# 2014-09-02_05-44-381.net
KiCad netlist of a schematic drawn in Altium Designer
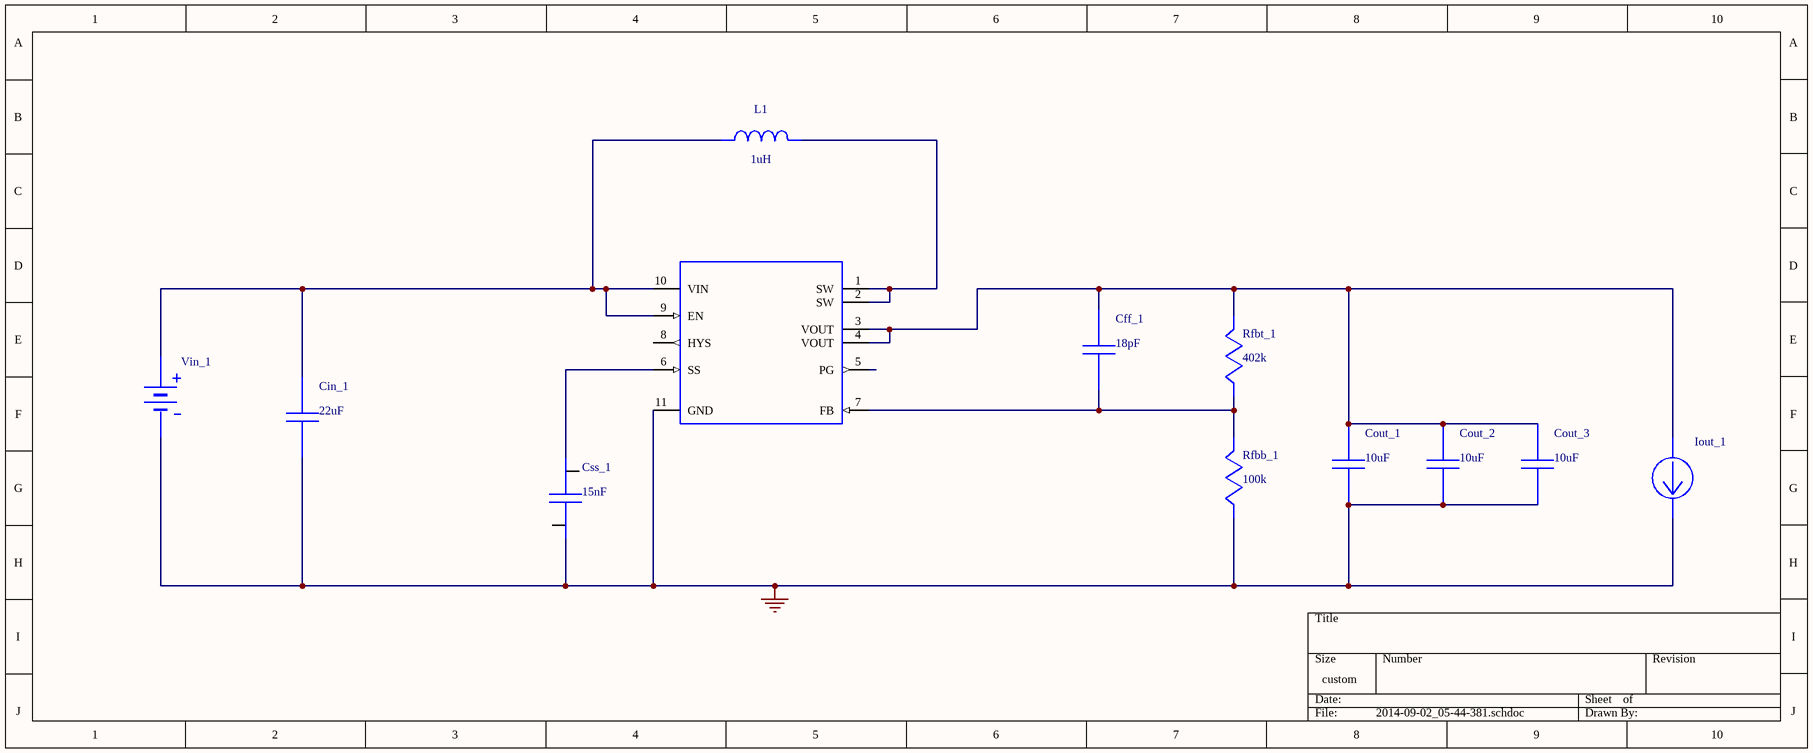
[diagram p0: 2014-09-02_05-44-381.schdoc]

(export (version "E")
  (design (tool "Eeschema 10.0.6"))
  (components
    (comp (ref "Cff_1")
      (value "18pF")
      (description "C0603C180J5GACTU")
      (libsource (lib "TI WEBENCH") (part "Cff_1"))
    )
    (comp (ref "Cin_1")
      (value "22uF")
      (description "C2012X5R0J226M")
      (libsource (lib "TI WEBENCH") (part "Cin_1"))
    )
    (comp (ref "Cout_1")
      (value "10uF")
      (description "GRM21BR61A106KE1")
      (fields (field (name "MANUFACTURER PART NUMBER") "GRM21BR61A106KE19L"))
      (libsource (lib "TI WEBENCH") (part "Cout_1"))
    )
    (comp (ref "Cout_2")
      (value "10uF")
      (description "GRM21BR61A106KE1")
      (fields (field (name "MANUFACTURER PART NUMBER") "GRM21BR61A106KE19L"))
      (libsource (lib "TI WEBENCH") (part "Cout_2"))
    )
    (comp (ref "Cout_3")
      (value "10uF")
      (description "GRM21BR61A106KE1")
      (fields (field (name "MANUFACTURER PART NUMBER") "GRM21BR61A106KE19L"))
      (libsource (lib "TI WEBENCH") (part "Cout_3"))
    )
    (comp (ref "Css_1")
      (value "15nF")
      (description "GRM155R71C153KA0")
      (fields (field (name "MANUFACTURER PART NUMBER") "GRM155R71C153KA01D"))
      (libsource (lib "TI WEBENCH") (part "Css_1"))
    )
    (comp (ref "Iout_1") (value "WB_CURRENT_LOAD") (libsource (lib "TI WEBENCH") (part "Iout_1")))
    (comp (ref "L1") (value "1uH") (description "SRU1028-1R0Y") (libsource (lib "TI WEBENCH") (part "L1")))
    (comp (ref "Rfbb_1")
      (value "100k")
      (description "CRCW0402100KFKED")
      (libsource (lib "TI WEBENCH") (part "Rfbb_1"))
    )
    (comp (ref "Rfbt_1")
      (value "402k")
      (description "CRCW0402402KFKED")
      (libsource (lib "TI WEBENCH") (part "Rfbt_1"))
    )
    (comp (ref "U1") (value "TPS61230DRCR") (libsource (lib "TI WEBENCH") (part "U1")))
    (comp (ref "Vin_1") (value "WB_BATTERY") (libsource (lib "TI WEBENCH") (part "Vin_1")))
  )
  (nets
    (net (code "1") (name "0") (class "Default")
      (node (ref "Cin_1") (pin "2") (pinfunction "2_2") (pintype "passive"))
      (node (ref "Cout_1") (pin "2") (pinfunction "2_2") (pintype "passive"))
      (node (ref "Cout_2") (pin "2") (pinfunction "2_2") (pintype "passive"))
      (node (ref "Cout_3") (pin "2") (pinfunction "2_2") (pintype "passive"))
      (node (ref "Iout_1") (pin "2") (pinfunction "-_2") (pintype "passive"))
      (node (ref "Rfbb_1") (pin "2") (pinfunction "2_2") (pintype "passive"))
      (node (ref "U1") (pin "11") (pinfunction "GND_11") (pintype "power_in"))
      (node (ref "Vin_1") (pin "2") (pinfunction "-_2") (pintype "passive"))
    )
    (net (code "2") (name "Net-(Iout_1-+)") (class "Default")
      (node (ref "Cff_1") (pin "1") (pinfunction "1_1") (pintype "passive"))
      (node (ref "Cout_1") (pin "1") (pinfunction "1_1") (pintype "passive"))
      (node (ref "Cout_2") (pin "1") (pinfunction "1_1") (pintype "passive"))
      (node (ref "Cout_3") (pin "1") (pinfunction "1_1") (pintype "passive"))
      (node (ref "Iout_1") (pin "1") (pinfunction "+_1") (pintype "passive"))
      (node (ref "Rfbt_1") (pin "1") (pinfunction "1_1") (pintype "passive"))
      (node (ref "U1") (pin "3") (pinfunction "VOUT_3") (pintype "power_in"))
      (node (ref "U1") (pin "4") (pinfunction "VOUT_4") (pintype "power_in"))
    )
    (net (code "3") (name "Net-(L1-Pad1)") (class "Default")
      (node (ref "L1") (pin "1") (pinfunction "1_1") (pintype "passive"))
      (node (ref "U1") (pin "1") (pinfunction "SW_1") (pintype "power_in"))
      (node (ref "U1") (pin "2") (pinfunction "SW_2") (pintype "power_in"))
    )
    (net (code "4") (name "Net-(U1-EN)") (class "Default")
      (node (ref "Cin_1") (pin "1") (pinfunction "1_1") (pintype "passive"))
      (node (ref "L1") (pin "2") (pinfunction "2_2") (pintype "passive"))
      (node (ref "U1") (pin "10") (pinfunction "VIN_10") (pintype "power_in"))
      (node (ref "U1") (pin "9") (pinfunction "EN_9") (pintype "input"))
      (node (ref "Vin_1") (pin "1") (pinfunction "+_1") (pintype "passive"))
    )
    (net (code "5") (name "Net-(U1-FB)") (class "Default")
      (node (ref "Cff_1") (pin "2") (pinfunction "2_2") (pintype "passive"))
      (node (ref "Rfbb_1") (pin "1") (pinfunction "1_1") (pintype "passive"))
      (node (ref "Rfbt_1") (pin "2") (pinfunction "2_2") (pintype "passive"))
      (node (ref "U1") (pin "7") (pinfunction "FB_7") (pintype "input"))
    )
    (net (code "6") (name "unconnected-(Css_1-Pad1)") (class "Default")
      (node (ref "Css_1") (pin "1") (pinfunction "1_1") (pintype "passive"))
    )
    (net (code "7") (name "unconnected-(Css_1-Pad2)") (class "Default")
      (node (ref "Css_1") (pin "2") (pinfunction "2_2") (pintype "passive"))
    )
    (net (code "8") (name "unconnected-(U1-HYS-Pad8)") (class "Default")
      (node (ref "U1") (pin "8") (pinfunction "HYS_8") (pintype "output"))
    )
    (net (code "9") (name "unconnected-(U1-PG-Pad5)") (class "Default")
      (node (ref "U1") (pin "5") (pinfunction "PG_5") (pintype "output"))
    )
    (net (code "10") (name "unconnected-(U1-SS-Pad6)") (class "Default")
      (node (ref "U1") (pin "6") (pinfunction "SS_6") (pintype "input"))
    )
  )
)
